# analog.net
KiCad netlist of a schematic drawn in Altium Designer
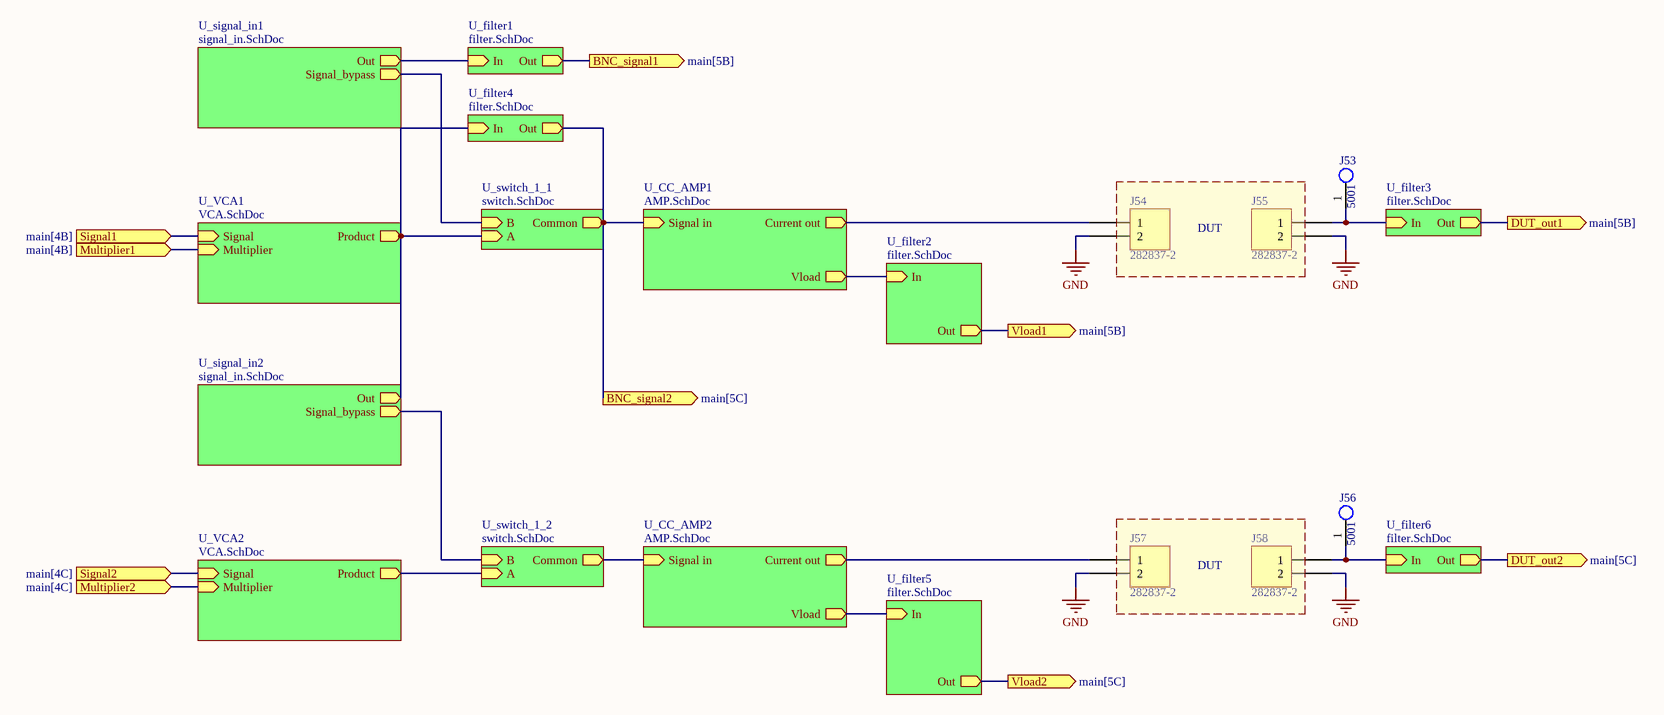
[diagram p0: analog.SchDoc]

(export (version "E")
  (design (tool "Eeschema 10.0.6"))
  (components
    (comp (ref "J53")
      (value "5001")
      (footprint "FP-5001-MFG")
      (description "PC TEST POINT MINIATURE BLACK")
      (libsource (lib "za_koncar") (part "CMP-2000-05181-2"))
    )
    (comp (ref "J54")
      (value "282837-2")
      (footprint "TE 282837-2")
      (description "TERM BLK 2P SIDE ENT 5.08MM PCB")
      (fields (field (name "MANUFACTURER") "TE Connectivity AMP Connectors") (field (name "VOLTAGE") "300 V"))
      (libsource (lib "Celestial Altium Library - altium_library") (part "2 Pin"))
    )
    (comp (ref "J55")
      (value "282837-2")
      (footprint "TE 282837-2")
      (description "TERM BLK 2P SIDE ENT 5.08MM PCB")
      (fields (field (name "MANUFACTURER") "TE Connectivity AMP Connectors") (field (name "VOLTAGE") "300 V"))
      (libsource (lib "") (part "2 Pin_1"))
    )
    (comp (ref "J56")
      (value "5001")
      (footprint "FP-5001-MFG")
      (description "PC TEST POINT MINIATURE BLACK")
      (libsource (lib "za_koncar") (part "CMP-2000-05181-2"))
    )
    (comp (ref "J57")
      (value "282837-2")
      (footprint "TE 282837-2")
      (description "TERM BLK 2P SIDE ENT 5.08MM PCB")
      (fields (field (name "MANUFACTURER") "TE Connectivity AMP Connectors") (field (name "VOLTAGE") "300 V"))
      (libsource (lib "Celestial Altium Library - altium_library") (part "2 Pin"))
    )
    (comp (ref "J58")
      (value "282837-2")
      (footprint "TE 282837-2")
      (description "TERM BLK 2P SIDE ENT 5.08MM PCB")
      (fields (field (name "MANUFACTURER") "TE Connectivity AMP Connectors") (field (name "VOLTAGE") "300 V"))
      (libsource (lib "") (part "2 Pin_1"))
    )
  )
  (nets
    (net (code "4") (name "/Current out") (class "Default")
      (node (ref "J57") (pin "1") (pinfunction "1_1") (pintype "passive"))
    )
    (net (code "5") (name "/Current out_1") (class "Default")
      (node (ref "J54") (pin "1") (pinfunction "1_1") (pintype "passive"))
    )
    (net (code "8") (name "/In") (class "Default")
      (node (ref "J53") (pin "1") (pinfunction "1_1") (pintype "passive"))
      (node (ref "J55") (pin "1") (pinfunction "1_1") (pintype "passive"))
    )
    (net (code "9") (name "/In_1") (class "Default")
      (node (ref "J56") (pin "1") (pinfunction "1_1") (pintype "passive"))
      (node (ref "J58") (pin "1") (pinfunction "1_1") (pintype "passive"))
    )
    (net (code "23") (name "GND") (class "Default")
      (node (ref "J54") (pin "2") (pinfunction "2_2") (pintype "passive"))
      (node (ref "J55") (pin "2") (pinfunction "2_2") (pintype "passive"))
      (node (ref "J57") (pin "2") (pinfunction "2_2") (pintype "passive"))
      (node (ref "J58") (pin "2") (pinfunction "2_2") (pintype "passive"))
    )
  )
)
